# RC.net
KiCad netlist of a schematic drawn in Altium Designer
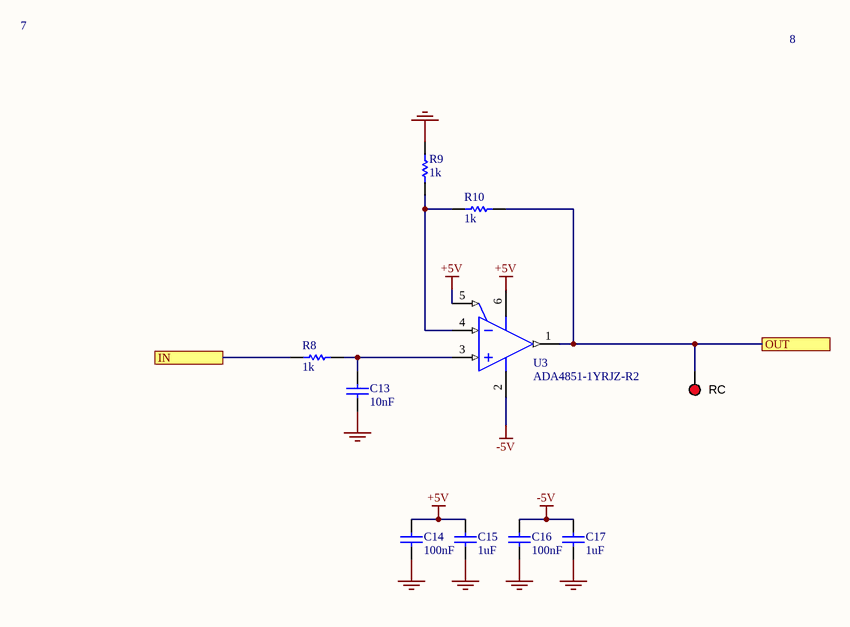
[diagram p0: RC.SchDoc]

(export (version "E")
  (design (tool "Eeschema 10.0.6"))
  (components
    (comp (ref "C13")
      (value "10nF")
      (footprint "CAPC0603(1608)100_N")
      (description "10nF Film")
      (fields (field (name "TOLERANCE") "Â±20%"))
      (libsource (lib "Altium Content Vault") (part "CAP"))
    )
    (comp (ref "C14")
      (value "100nF")
      (footprint "CAPC0603(1608)100_N")
      (description "CAP 100nF 25V ±20% 0603 (1608 Metric) Thickness 1mm SMD")
      (fields (field (name "TOLERANCE") "Â±20%"))
      (libsource (lib "Altium Content Vault") (part "CAP"))
    )
    (comp (ref "C15")
      (value "1uF")
      (footprint "CAPC0603(1608)100_N")
      (description "CAP 1uF 25V ±20% 0603 (1608 Metric) Thickness 1mm SMD")
      (fields (field (name "TOLERANCE") "Â±20%"))
      (libsource (lib "Altium Content Vault") (part "CAP"))
    )
    (comp (ref "C16")
      (value "100nF")
      (footprint "CAPC0603(1608)100_N")
      (description "CAP 100nF 25V ±20% 0603 (1608 Metric) Thickness 1mm SMD")
      (fields (field (name "TOLERANCE") "Â±20%"))
      (libsource (lib "Altium Content Vault") (part "CAP"))
    )
    (comp (ref "C17")
      (value "1uF")
      (footprint "CAPC0603(1608)100_N")
      (description "CAP 1uF 25V ±20% 0603 (1608 Metric) Thickness 1mm SMD")
      (fields (field (name "TOLERANCE") "Â±20%"))
      (libsource (lib "Altium Content Vault") (part "CAP"))
    )
    (comp (ref "R8")
      (value "1k")
      (footprint "RESC0603(1608)_N")
      (description "1k 1% Metal film")
      (fields (field (name "TOLERANCE") "1 %") (field (name "POWER") "0.1 W"))
      (libsource (lib "Altium Content Vault") (part "RES"))
    )
    (comp (ref "R9")
      (value "1k")
      (footprint "RESC0603(1608)_N")
      (description "1k 1% Metal film")
      (fields (field (name "TOLERANCE") "1 %") (field (name "POWER") "0.1 W"))
      (libsource (lib "Altium Content Vault") (part "RES"))
    )
    (comp (ref "R10")
      (value "1k")
      (footprint "RESC0603(1608)_N")
      (description "1k 1% Metal film")
      (fields (field (name "TOLERANCE") "1 %") (field (name "POWER") "0.1 W"))
      (libsource (lib "Altium Content Vault") (part "RES"))
    )
    (comp (ref "RC")
      (value "5010")
      (footprint "KSTN-5010_V")
      (description "Test Point, Red, Through Hole, RoHS, Bulk")
      (libsource (lib "Altium Content Vault") (part "TESTPOINT_RED"))
    )
    (comp (ref "U3")
      (value "ADA4851-1YRJZ-R2")
      (footprint "ADI-RJ-6_N")
      (fields (field (name "GENERIC PART NUMBER") "ADA4851-1") (field (name "MANUFACTURER") "Analog Devices"))
      (libsource (lib "Altium Content Vault") (part "ADI-ADA48X1-1-RJ-6"))
    )
  )
  (nets
    (net (code "1") (name "+5V") (class "Default")
      (node (ref "C14") (pin "2") (pinfunction "2_2") (pintype "passive"))
      (node (ref "C15") (pin "2") (pinfunction "2_2") (pintype "passive"))
      (node (ref "U3") (pin "5") (pinfunction "~{POWER_DOWN}_5") (pintype "input"))
      (node (ref "U3") (pin "6") (pinfunction "+VS_6") (pintype "power_in"))
    )
    (net (code "2") (name "-5V") (class "Default")
      (node (ref "C16") (pin "2") (pinfunction "2_2") (pintype "passive"))
      (node (ref "C17") (pin "2") (pinfunction "2_2") (pintype "passive"))
      (node (ref "U3") (pin "2") (pinfunction "-VS_2") (pintype "power_in"))
    )
    (net (code "3") (name "/IN") (class "Default")
      (node (ref "R8") (pin "2") (pinfunction "2_2") (pintype "passive"))
    )
    (net (code "4") (name "/OUT") (class "Default")
      (node (ref "R10") (pin "1") (pinfunction "1_1") (pintype "passive"))
      (node (ref "RC") (pin "1") (pinfunction "1_1") (pintype "passive"))
      (node (ref "U3") (pin "1") (pinfunction "VOUT_1") (pintype "output"))
    )
    (net (code "5") (name "GND") (class "Default")
      (node (ref "C13") (pin "2") (pinfunction "2_2") (pintype "passive"))
      (node (ref "C14") (pin "1") (pinfunction "1_1") (pintype "passive"))
      (node (ref "C15") (pin "1") (pinfunction "1_1") (pintype "passive"))
      (node (ref "C16") (pin "1") (pinfunction "1_1") (pintype "passive"))
      (node (ref "C17") (pin "1") (pinfunction "1_1") (pintype "passive"))
      (node (ref "R9") (pin "1") (pinfunction "1_1") (pintype "passive"))
    )
    (net (code "6") (name "Net-(U3-+IN)") (class "Default")
      (node (ref "C13") (pin "1") (pinfunction "1_1") (pintype "passive"))
      (node (ref "R8") (pin "1") (pinfunction "1_1") (pintype "passive"))
      (node (ref "U3") (pin "3") (pinfunction "+IN_3") (pintype "input"))
    )
    (net (code "7") (name "Net-(U3--IN)") (class "Default")
      (node (ref "R10") (pin "2") (pinfunction "2_2") (pintype "passive"))
      (node (ref "R9") (pin "2") (pinfunction "2_2") (pintype "passive"))
      (node (ref "U3") (pin "4") (pinfunction "-IN_4") (pintype "input"))
    )
  )
)
